# SCH_ESPHome_Fan.net
KiCad netlist of a schematic drawn in Altium Designer
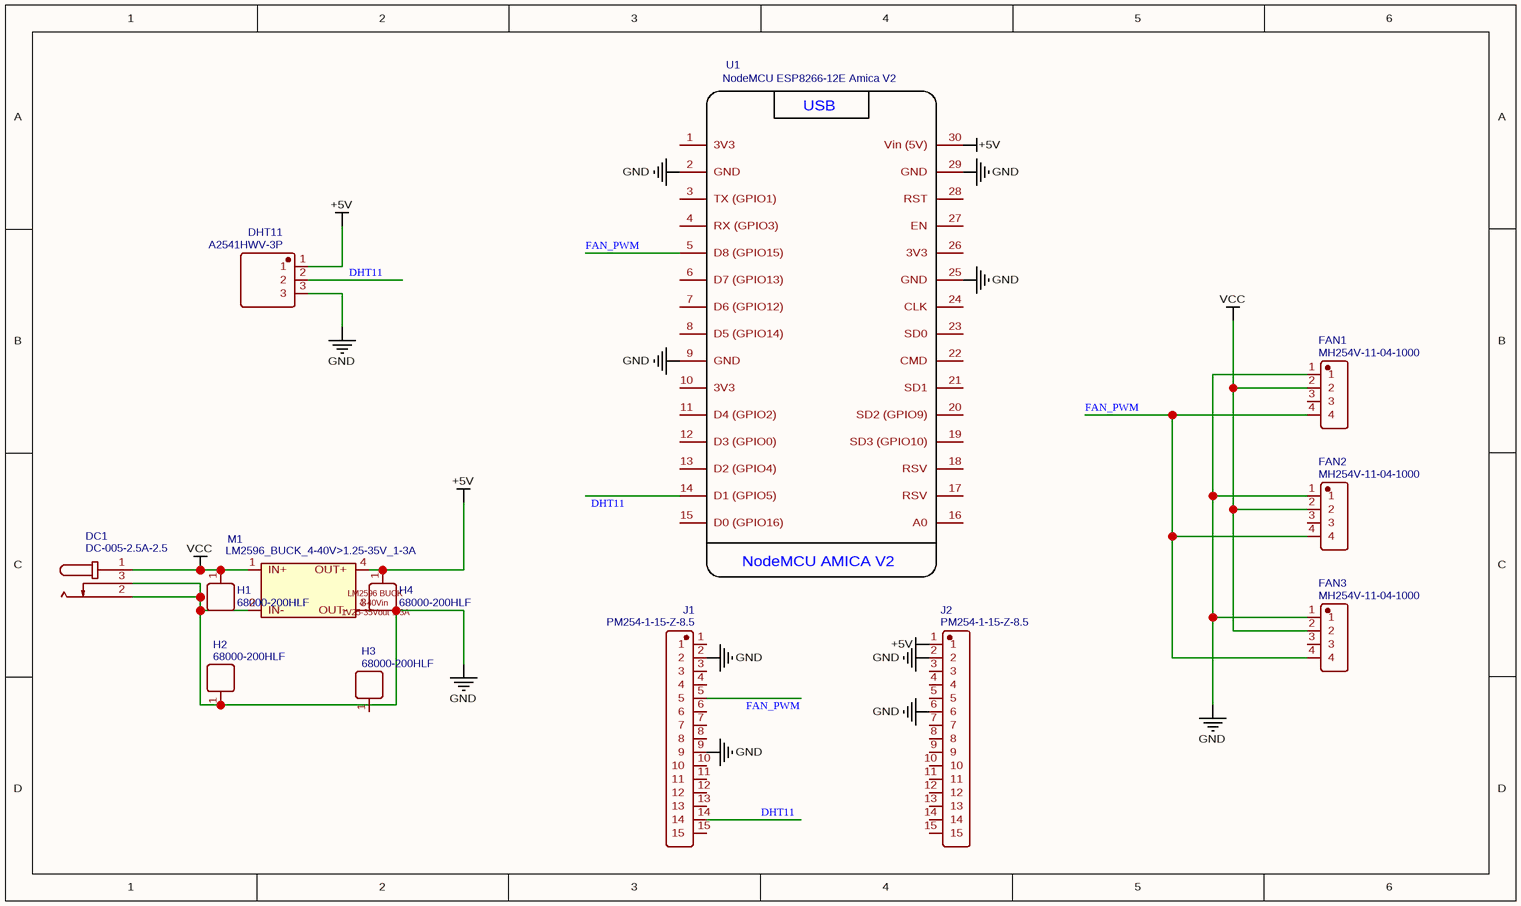
[diagram p0: SCH_ESPHome Fan.schdoc]

(export (version "E")
  (design (tool "Eeschema 10.0.6"))
  (components
    (comp (ref "DC1")
      (value "DC-005-2.5A-2.5")
      (fields (field (name "BOM_SUPPLIER PART") "C319098") (field (name "CONTRIBUTOR") "LCSC"))
      (libsource (lib "altium-import") (part "root_0_DC-005-2.5A-2.5_"))
    )
    (comp (ref "DHT11")
      (value "A2541HWV-3P")
      (fields (field (name "BOM_SUPPLIER PART") "C225500") (field (name "CONTRIBUTOR") "LCSC"))
      (libsource (lib "altium-import") (part "root_0_A2541HWV-3P_"))
    )
    (comp (ref "FAN1")
      (value "MH254V-11-04-1000")
      (fields (field (name "BOM_SUPPLIER PART") "C509261") (field (name "CONTRIBUTOR") "LCSC"))
      (libsource (lib "altium-import") (part "root_0_MH254V-11-04-1000_"))
    )
    (comp (ref "FAN2")
      (value "MH254V-11-04-1000")
      (fields (field (name "BOM_SUPPLIER PART") "C509261") (field (name "CONTRIBUTOR") "LCSC"))
      (libsource (lib "altium-import") (part "root_0_MH254V-11-04-1000_"))
    )
    (comp (ref "FAN3")
      (value "MH254V-11-04-1000")
      (fields (field (name "BOM_SUPPLIER PART") "C509261") (field (name "CONTRIBUTOR") "LCSC"))
      (libsource (lib "altium-import") (part "root_0_MH254V-11-04-1000_"))
    )
    (comp (ref "H1")
      (value "68000-200HLF")
      (fields (field (name "BOM_SUPPLIER PART") "C213187") (field (name "CONTRIBUTOR") "LCSC"))
      (libsource (lib "altium-import") (part "root_3_68000-200HLF_"))
    )
    (comp (ref "H2")
      (value "68000-200HLF")
      (fields (field (name "BOM_SUPPLIER PART") "C213187") (field (name "CONTRIBUTOR") "LCSC"))
      (libsource (lib "altium-import") (part "root_1_68000-200HLF_"))
    )
    (comp (ref "H3")
      (value "68000-200HLF")
      (fields (field (name "BOM_SUPPLIER PART") "C213187") (field (name "CONTRIBUTOR") "LCSC"))
      (libsource (lib "altium-import") (part "root_1_68000-200HLF_"))
    )
    (comp (ref "H4")
      (value "68000-200HLF")
      (fields (field (name "BOM_SUPPLIER PART") "C213187") (field (name "CONTRIBUTOR") "LCSC"))
      (libsource (lib "altium-import") (part "root_3_68000-200HLF_"))
    )
    (comp (ref "J1")
      (value "PM254-1-15-Z-8.5")
      (fields (field (name "BOM_SUPPLIER PART") "C2897378") (field (name "CONTRIBUTOR") "LCSC"))
      (libsource (lib "altium-import") (part "root_0_PM254-1-15-Z-8.5_"))
    )
    (comp (ref "J2")
      (value "PM254-1-15-Z-8.5")
      (fields (field (name "BOM_SUPPLIER PART") "C2897378") (field (name "CONTRIBUTOR") "LCSC"))
      (libsource (lib "") (part "root_0_PM254-1-15-Z-8.5__1"))
    )
    (comp (ref "M1")
      (value "LM2596_BUCK_4-40V>1.25-35V_1-3A")
      (fields (field (name "CONTRIBUTOR") "scalak_s"))
      (libsource (lib "altium-import") (part "root_0_LM2596_BUCK_4-40V{gt}1.25-35V_1-3A_"))
    )
    (comp (ref "U1")
      (value "NodeMCU ESP8266-12E Amica V2")
      (fields
        (field (name "BOM_SUPPLIER PART") "nodemcu-v2")
        (field (name "CONTRIBUTOR") "irukard")
        (field (name "AUTHOR") "Krzysztof Daszuta")
      )
      (libsource (lib "altium-import") (part "root_0_NodeMCU ESP8266-12E Amica V2_"))
    )
  )
  (nets
    (net (code "1") (name "+5V") (class "Default")
      (node (ref "DHT11") (pin "1") (pinfunction "1_1") (pintype "passive"))
      (node (ref "H4") (pin "1") (pinfunction "1_1") (pintype "passive"))
      (node (ref "J2") (pin "1") (pinfunction "1_1") (pintype "passive"))
      (node (ref "M1") (pin "4") (pinfunction "OUT+_4") (pintype "passive"))
      (node (ref "U1") (pin "30") (pinfunction "Vin_(5V)_30") (pintype "passive"))
    )
    (net (code "2") (name "/DHT11") (class "Default")
      (node (ref "DHT11") (pin "2") (pinfunction "2_2") (pintype "passive"))
      (node (ref "J1") (pin "14") (pinfunction "14_14") (pintype "passive"))
      (node (ref "U1") (pin "14") (pinfunction "D1_(GPIO5)_14") (pintype "passive"))
    )
    (net (code "3") (name "/FAN_PWM") (class "Default")
      (node (ref "FAN1") (pin "4") (pinfunction "4_4") (pintype "passive"))
      (node (ref "FAN2") (pin "4") (pinfunction "4_4") (pintype "passive"))
      (node (ref "FAN3") (pin "4") (pinfunction "4_4") (pintype "passive"))
      (node (ref "J1") (pin "5") (pinfunction "5_5") (pintype "passive"))
      (node (ref "U1") (pin "5") (pinfunction "D8_(GPIO15)_5") (pintype "passive"))
    )
    (net (code "4") (name "GND") (class "Default")
      (node (ref "DC1") (pin "2") (pinfunction "2_2") (pintype "passive"))
      (node (ref "DC1") (pin "3") (pinfunction "3_3") (pintype "passive"))
      (node (ref "DHT11") (pin "3") (pinfunction "3_3") (pintype "passive"))
      (node (ref "FAN1") (pin "1") (pinfunction "1_1") (pintype "passive"))
      (node (ref "FAN2") (pin "1") (pinfunction "1_1") (pintype "passive"))
      (node (ref "FAN3") (pin "1") (pinfunction "1_1") (pintype "passive"))
      (node (ref "H2") (pin "1") (pinfunction "1_1") (pintype "passive"))
      (node (ref "J1") (pin "2") (pinfunction "2_2") (pintype "passive"))
      (node (ref "J1") (pin "9") (pinfunction "9_9") (pintype "passive"))
      (node (ref "J2") (pin "2") (pinfunction "2_2") (pintype "passive"))
      (node (ref "J2") (pin "6") (pinfunction "6_6") (pintype "passive"))
      (node (ref "M1") (pin "2") (pinfunction "IN-_2") (pintype "passive"))
      (node (ref "M1") (pin "3") (pinfunction "OUT-_3") (pintype "passive"))
      (node (ref "U1") (pin "2") (pinfunction "GND_2") (pintype "passive"))
      (node (ref "U1") (pin "25") (pinfunction "GND_25") (pintype "passive"))
      (node (ref "U1") (pin "29") (pinfunction "GND_29") (pintype "passive"))
      (node (ref "U1") (pin "9") (pinfunction "GND_9") (pintype "passive"))
    )
    (net (code "5") (name "VCC") (class "Default")
      (node (ref "DC1") (pin "1") (pinfunction "1_1") (pintype "passive"))
      (node (ref "FAN1") (pin "2") (pinfunction "2_2") (pintype "passive"))
      (node (ref "FAN2") (pin "2") (pinfunction "2_2") (pintype "passive"))
      (node (ref "FAN3") (pin "2") (pinfunction "2_2") (pintype "passive"))
      (node (ref "H1") (pin "1") (pinfunction "1_1") (pintype "passive"))
      (node (ref "M1") (pin "1") (pinfunction "IN+_1") (pintype "passive"))
    )
    (net (code "6") (name "unconnected-(FAN1-Pad3)") (class "Default")
      (node (ref "FAN1") (pin "3") (pinfunction "3_3") (pintype "passive"))
    )
    (net (code "7") (name "unconnected-(FAN2-Pad3)") (class "Default")
      (node (ref "FAN2") (pin "3") (pinfunction "3_3") (pintype "passive"))
    )
    (net (code "8") (name "unconnected-(FAN3-Pad3)") (class "Default")
      (node (ref "FAN3") (pin "3") (pinfunction "3_3") (pintype "passive"))
    )
    (net (code "9") (name "unconnected-(H3-Pad1)") (class "Default")
      (node (ref "H3") (pin "1") (pinfunction "1_1") (pintype "passive"))
    )
    (net (code "10") (name "unconnected-(J1-Pad1)") (class "Default")
      (node (ref "J1") (pin "1") (pinfunction "1_1") (pintype "passive"))
    )
    (net (code "11") (name "unconnected-(J1-Pad3)") (class "Default")
      (node (ref "J1") (pin "3") (pinfunction "3_3") (pintype "passive"))
    )
    (net (code "12") (name "unconnected-(J1-Pad4)") (class "Default")
      (node (ref "J1") (pin "4") (pinfunction "4_4") (pintype "passive"))
    )
    (net (code "13") (name "unconnected-(J1-Pad6)") (class "Default")
      (node (ref "J1") (pin "6") (pinfunction "6_6") (pintype "passive"))
    )
    (net (code "14") (name "unconnected-(J1-Pad7)") (class "Default")
      (node (ref "J1") (pin "7") (pinfunction "7_7") (pintype "passive"))
    )
    (net (code "15") (name "unconnected-(J1-Pad8)") (class "Default")
      (node (ref "J1") (pin "8") (pinfunction "8_8") (pintype "passive"))
    )
    (net (code "16") (name "unconnected-(J1-Pad10)") (class "Default")
      (node (ref "J1") (pin "10") (pinfunction "10_10") (pintype "passive"))
    )
    (net (code "17") (name "unconnected-(J1-Pad11)") (class "Default")
      (node (ref "J1") (pin "11") (pinfunction "11_11") (pintype "passive"))
    )
    (net (code "18") (name "unconnected-(J1-Pad12)") (class "Default")
      (node (ref "J1") (pin "12") (pinfunction "12_12") (pintype "passive"))
    )
    (net (code "19") (name "unconnected-(J1-Pad13)") (class "Default")
      (node (ref "J1") (pin "13") (pinfunction "13_13") (pintype "passive"))
    )
    (net (code "20") (name "unconnected-(J1-Pad15)") (class "Default")
      (node (ref "J1") (pin "15") (pinfunction "15_15") (pintype "passive"))
    )
    (net (code "21") (name "unconnected-(J2-Pad3)") (class "Default")
      (node (ref "J2") (pin "3") (pinfunction "3_3") (pintype "passive"))
    )
    (net (code "22") (name "unconnected-(J2-Pad4)") (class "Default")
      (node (ref "J2") (pin "4") (pinfunction "4_4") (pintype "passive"))
    )
    (net (code "23") (name "unconnected-(J2-Pad5)") (class "Default")
      (node (ref "J2") (pin "5") (pinfunction "5_5") (pintype "passive"))
    )
    (net (code "24") (name "unconnected-(J2-Pad7)") (class "Default")
      (node (ref "J2") (pin "7") (pinfunction "7_7") (pintype "passive"))
    )
    (net (code "25") (name "unconnected-(J2-Pad8)") (class "Default")
      (node (ref "J2") (pin "8") (pinfunction "8_8") (pintype "passive"))
    )
    (net (code "26") (name "unconnected-(J2-Pad9)") (class "Default")
      (node (ref "J2") (pin "9") (pinfunction "9_9") (pintype "passive"))
    )
    (net (code "27") (name "unconnected-(J2-Pad10)") (class "Default")
      (node (ref "J2") (pin "10") (pinfunction "10_10") (pintype "passive"))
    )
    (net (code "28") (name "unconnected-(J2-Pad11)") (class "Default")
      (node (ref "J2") (pin "11") (pinfunction "11_11") (pintype "passive"))
    )
    (net (code "29") (name "unconnected-(J2-Pad12)") (class "Default")
      (node (ref "J2") (pin "12") (pinfunction "12_12") (pintype "passive"))
    )
    (net (code "30") (name "unconnected-(J2-Pad13)") (class "Default")
      (node (ref "J2") (pin "13") (pinfunction "13_13") (pintype "passive"))
    )
    (net (code "31") (name "unconnected-(J2-Pad14)") (class "Default")
      (node (ref "J2") (pin "14") (pinfunction "14_14") (pintype "passive"))
    )
    (net (code "32") (name "unconnected-(J2-Pad15)") (class "Default")
      (node (ref "J2") (pin "15") (pinfunction "15_15") (pintype "passive"))
    )
    (net (code "33") (name "unconnected-(U1-3V3-Pad1)") (class "Default")
      (node (ref "U1") (pin "1") (pinfunction "3V3_1") (pintype "passive"))
    )
    (net (code "34") (name "unconnected-(U1-3V3-Pad10)") (class "Default")
      (node (ref "U1") (pin "10") (pinfunction "3V3_10") (pintype "passive"))
    )
    (net (code "35") (name "unconnected-(U1-3V3-Pad26)") (class "Default")
      (node (ref "U1") (pin "26") (pinfunction "3V3_26") (pintype "passive"))
    )
    (net (code "36") (name "unconnected-(U1-A0-Pad16)") (class "Default")
      (node (ref "U1") (pin "16") (pinfunction "A0_16") (pintype "passive"))
    )
    (net (code "37") (name "unconnected-(U1-CLK-Pad24)") (class "Default")
      (node (ref "U1") (pin "24") (pinfunction "CLK_24") (pintype "passive"))
    )
    (net (code "38") (name "unconnected-(U1-CMD-Pad22)") (class "Default")
      (node (ref "U1") (pin "22") (pinfunction "CMD_22") (pintype "passive"))
    )
    (net (code "39") (name "unconnected-(U1-D0_(GPIO16)-Pad15)") (class "Default")
      (node (ref "U1") (pin "15") (pinfunction "D0_(GPIO16)_15") (pintype "passive"))
    )
    (net (code "40") (name "unconnected-(U1-D2_(GPIO4)-Pad13)") (class "Default")
      (node (ref "U1") (pin "13") (pinfunction "D2_(GPIO4)_13") (pintype "passive"))
    )
    (net (code "41") (name "unconnected-(U1-D3_(GPIO0)-Pad12)") (class "Default")
      (node (ref "U1") (pin "12") (pinfunction "D3_(GPIO0)_12") (pintype "passive"))
    )
    (net (code "42") (name "unconnected-(U1-D4_(GPIO2)-Pad11)") (class "Default")
      (node (ref "U1") (pin "11") (pinfunction "D4_(GPIO2)_11") (pintype "passive"))
    )
    (net (code "43") (name "unconnected-(U1-D5_(GPIO14)-Pad8)") (class "Default")
      (node (ref "U1") (pin "8") (pinfunction "D5_(GPIO14)_8") (pintype "passive"))
    )
    (net (code "44") (name "unconnected-(U1-D6_(GPIO12)-Pad7)") (class "Default")
      (node (ref "U1") (pin "7") (pinfunction "D6_(GPIO12)_7") (pintype "passive"))
    )
    (net (code "45") (name "unconnected-(U1-D7_(GPIO13)-Pad6)") (class "Default")
      (node (ref "U1") (pin "6") (pinfunction "D7_(GPIO13)_6") (pintype "passive"))
    )
    (net (code "46") (name "unconnected-(U1-EN-Pad27)") (class "Default")
      (node (ref "U1") (pin "27") (pinfunction "EN_27") (pintype "passive"))
    )
    (net (code "47") (name "unconnected-(U1-RST-Pad28)") (class "Default")
      (node (ref "U1") (pin "28") (pinfunction "RST_28") (pintype "passive"))
    )
    (net (code "48") (name "unconnected-(U1-RSV-Pad17)") (class "Default")
      (node (ref "U1") (pin "17") (pinfunction "RSV_17") (pintype "passive"))
    )
    (net (code "49") (name "unconnected-(U1-RSV-Pad18)") (class "Default")
      (node (ref "U1") (pin "18") (pinfunction "RSV_18") (pintype "passive"))
    )
    (net (code "50") (name "unconnected-(U1-RX_(GPIO3)-Pad4)") (class "Default")
      (node (ref "U1") (pin "4") (pinfunction "RX_(GPIO3)_4") (pintype "passive"))
    )
    (net (code "51") (name "unconnected-(U1-SD0-Pad23)") (class "Default")
      (node (ref "U1") (pin "23") (pinfunction "SD0_23") (pintype "passive"))
    )
    (net (code "52") (name "unconnected-(U1-SD1-Pad21)") (class "Default")
      (node (ref "U1") (pin "21") (pinfunction "SD1_21") (pintype "passive"))
    )
    (net (code "53") (name "unconnected-(U1-SD2_(GPIO9)-Pad20)") (class "Default")
      (node (ref "U1") (pin "20") (pinfunction "SD2_(GPIO9)_20") (pintype "passive"))
    )
    (net (code "54") (name "unconnected-(U1-SD3_(GPIO10)-Pad19)") (class "Default")
      (node (ref "U1") (pin "19") (pinfunction "SD3_(GPIO10)_19") (pintype "passive"))
    )
    (net (code "55") (name "unconnected-(U1-TX_(GPIO1)-Pad3)") (class "Default")
      (node (ref "U1") (pin "3") (pinfunction "TX_(GPIO1)_3") (pintype "passive"))
    )
  )
)
